# oresat0-mezzanine.net
KiCad netlist of a schematic drawn in EAGLE
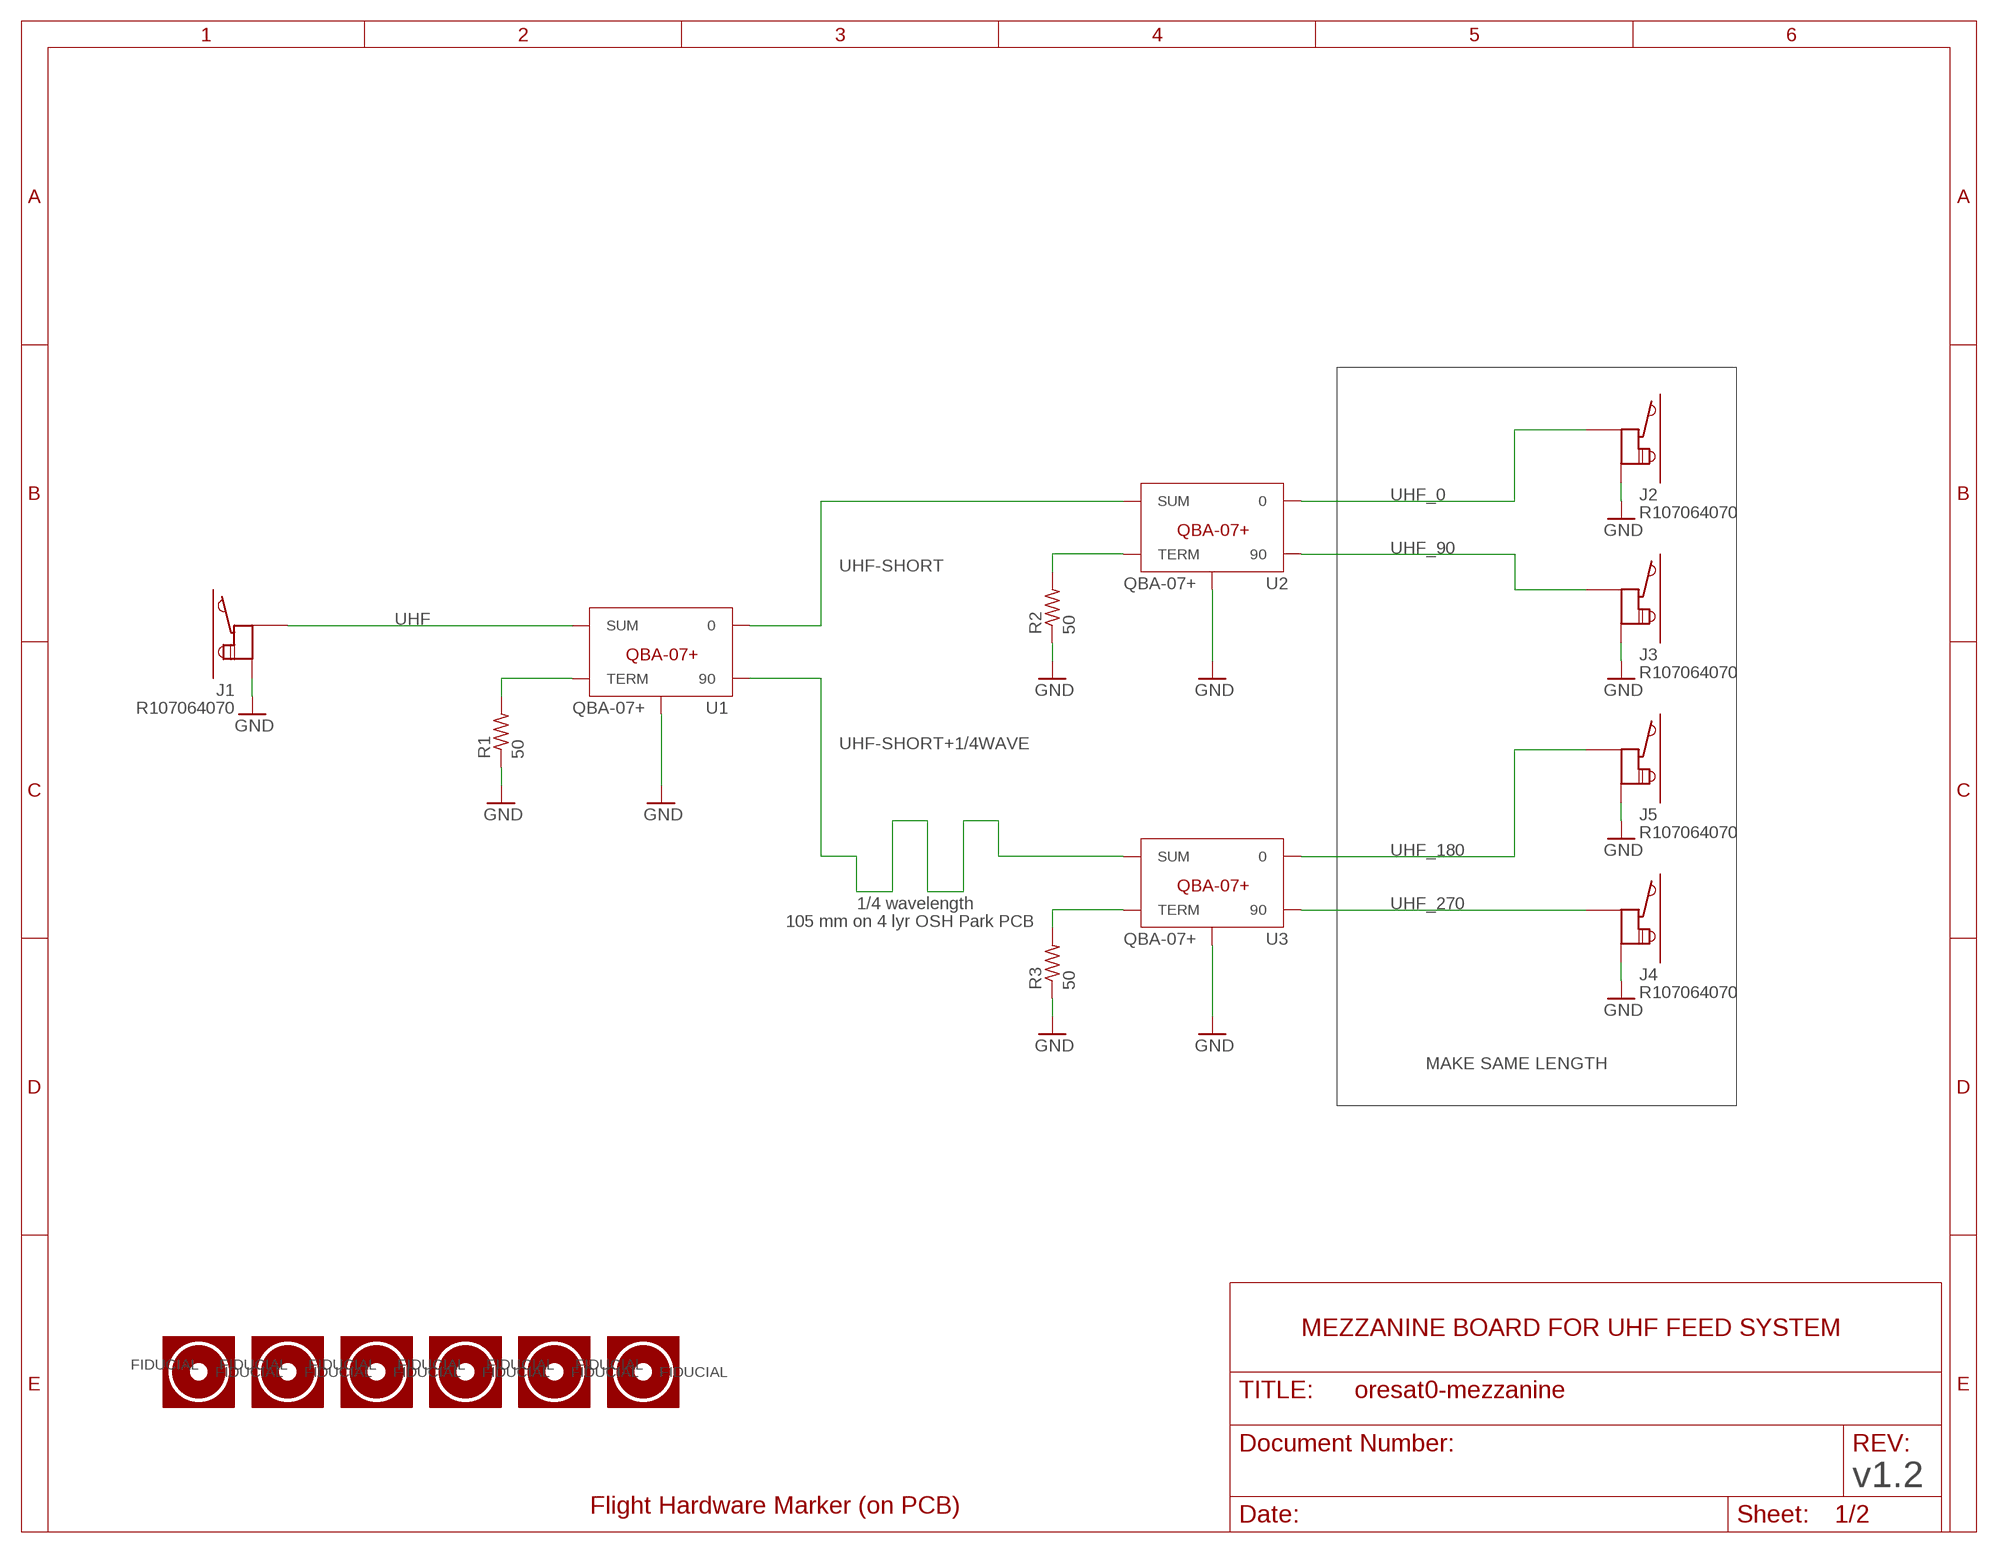
[diagram p0: schematic, sheet 1]
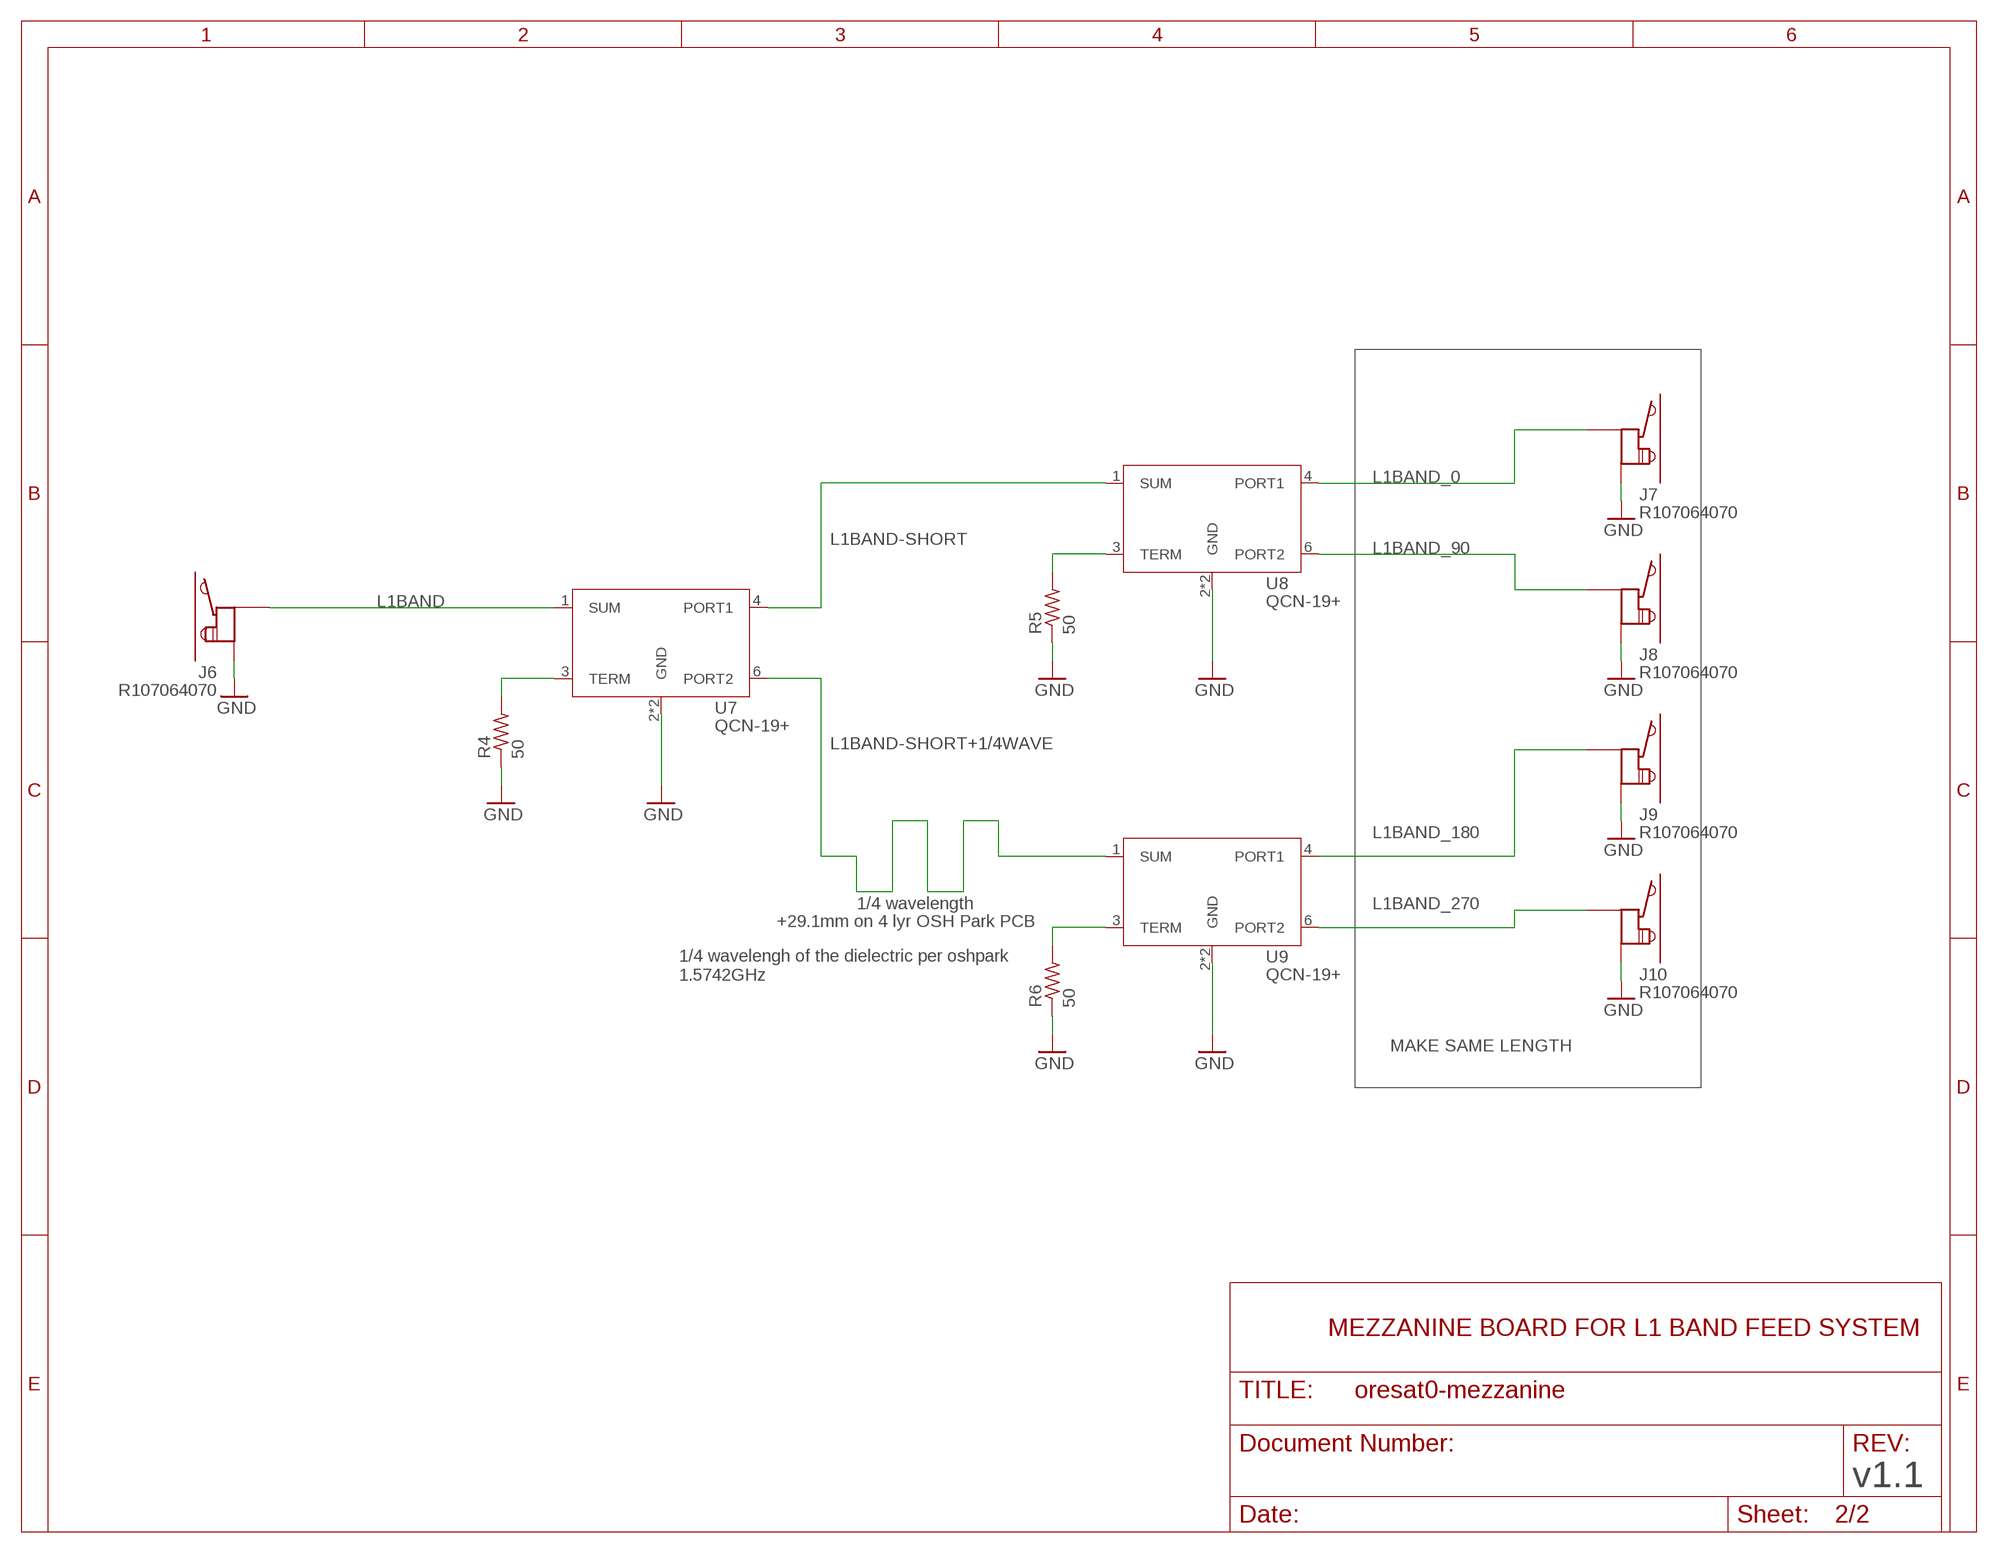
[diagram p1: schematic, sheet 2]

(export (version "E")
  (design (tool "Eeschema 10.0.6"))
  (components
    (comp (ref "J6")
      (value "R107064070")
      (footprint "eagle-import:R107064070_SOLDER")
      (fields (field (name "MFG") "Radiall"))
      (libsource (lib "eagle-import") (part "R107064070"))
    )
    (comp (ref "J7")
      (value "R107064070")
      (footprint "eagle-import:R107064070_SOLDER")
      (fields (field (name "MFG") "Radiall"))
      (libsource (lib "eagle-import") (part "R107064070"))
    )
    (comp (ref "J8")
      (value "R107064070")
      (footprint "eagle-import:R107064070_SOLDER")
      (fields (field (name "MFG") "Radiall"))
      (libsource (lib "eagle-import") (part "R107064070"))
    )
    (comp (ref "J9")
      (value "R107064070")
      (footprint "eagle-import:R107064070_SOLDER")
      (fields (field (name "MFG") "Radiall"))
      (libsource (lib "eagle-import") (part "R107064070"))
    )
    (comp (ref "J10")
      (value "R107064070")
      (footprint "eagle-import:R107064070_SOLDER")
      (fields (field (name "MFG") "Radiall"))
      (libsource (lib "eagle-import") (part "R107064070"))
    )
    (comp (ref "R4")
      (value "50")
      (footprint "eagle-import:.0603-C-NOSILK")
      (libsource (lib "eagle-import") (part "R-US_0603-C-NOSILK"))
    )
    (comp (ref "R5")
      (value "50")
      (footprint "eagle-import:.0603-C-NOSILK")
      (libsource (lib "eagle-import") (part "R-US_0603-C-NOSILK"))
    )
    (comp (ref "R6")
      (value "50")
      (footprint "eagle-import:.0603-C-NOSILK")
      (libsource (lib "eagle-import") (part "R-US_0603-C-NOSILK"))
    )
    (comp (ref "U7")
      (value "QCN-19+")
      (footprint "eagle-import:QCN-XXX+")
      (fields (field (name "MFG") "Mini-Circuits"))
      (libsource (lib "eagle-import") (part "QCN-XXX+"))
    )
    (comp (ref "U8")
      (value "QCN-19+")
      (footprint "eagle-import:QCN-XXX+")
      (fields (field (name "MFG") "Mini-Circuits"))
      (libsource (lib "eagle-import") (part "QCN-XXX+"))
    )
    (comp (ref "U9")
      (value "QCN-19+")
      (footprint "eagle-import:QCN-XXX+")
      (fields (field (name "MFG") "Mini-Circuits"))
      (libsource (lib "eagle-import") (part "QCN-XXX+"))
    )
    (comp (ref "FIDUCIAL1")
      (value "FIDUCIAL-1.0X2.0")
      (footprint "eagle-import:FIDUCIAL-1.0X2.0")
      (libsource (lib "eagle-import") (part "FIDUCIAL-1.0X2.0"))
    )
    (comp (ref "FIDUCIAL2")
      (value "FIDUCIAL-1.0X2.0")
      (footprint "eagle-import:FIDUCIAL-1.0X2.0")
      (libsource (lib "eagle-import") (part "FIDUCIAL-1.0X2.0"))
    )
    (comp (ref "FIDUCIAL3")
      (value "FIDUCIAL-1.0X2.0")
      (footprint "eagle-import:FIDUCIAL-1.0X2.0")
      (libsource (lib "eagle-import") (part "FIDUCIAL-1.0X2.0"))
    )
    (comp (ref "FIDUCIAL4")
      (value "FIDUCIAL-1.0X2.0")
      (footprint "eagle-import:FIDUCIAL-1.0X2.0")
      (libsource (lib "eagle-import") (part "FIDUCIAL-1.0X2.0"))
    )
    (comp (ref "FIDUCIAL6")
      (value "FIDUCIAL-1.0X2.0")
      (footprint "eagle-import:FIDUCIAL-1.0X2.0")
      (libsource (lib "eagle-import") (part "FIDUCIAL-1.0X2.0"))
    )
    (comp (ref "FIDUCIAL7")
      (value "FIDUCIAL-1.0X2.0")
      (footprint "eagle-import:FIDUCIAL-1.0X2.0")
      (libsource (lib "eagle-import") (part "FIDUCIAL-1.0X2.0"))
    )
    (comp (ref "J1")
      (value "R107064070")
      (footprint "eagle-import:R107064070_SOLDER")
      (fields (field (name "MFG") "Radiall"))
      (libsource (lib "eagle-import") (part "R107064070"))
    )
    (comp (ref "J2")
      (value "R107064070")
      (footprint "eagle-import:R107064070_SOLDER")
      (fields (field (name "MFG") "Radiall"))
      (libsource (lib "eagle-import") (part "R107064070"))
    )
    (comp (ref "J3")
      (value "R107064070")
      (footprint "eagle-import:R107064070_SOLDER")
      (fields (field (name "MFG") "Radiall"))
      (libsource (lib "eagle-import") (part "R107064070"))
    )
    (comp (ref "J4")
      (value "R107064070")
      (footprint "eagle-import:R107064070_SOLDER")
      (fields (field (name "MFG") "Radiall"))
      (libsource (lib "eagle-import") (part "R107064070"))
    )
    (comp (ref "J5")
      (value "R107064070")
      (footprint "eagle-import:R107064070_SOLDER")
      (fields (field (name "MFG") "Radiall"))
      (libsource (lib "eagle-import") (part "R107064070"))
    )
    (comp (ref "R1")
      (value "50")
      (footprint "eagle-import:.0603-C-NOSILK")
      (libsource (lib "eagle-import") (part "R-US_0603-C-NOSILK"))
    )
    (comp (ref "R2")
      (value "50")
      (footprint "eagle-import:.0603-C-NOSILK")
      (libsource (lib "eagle-import") (part "R-US_0603-C-NOSILK"))
    )
    (comp (ref "R3")
      (value "50")
      (footprint "eagle-import:.0603-C-NOSILK")
      (libsource (lib "eagle-import") (part "R-US_0603-C-NOSILK"))
    )
    (comp (ref "U$1")
      (value "FLIGHMARKERNEW")
      (footprint "eagle-import:FLIGHTMARKER_NEW_BOARDS")
      (libsource (lib "eagle-import") (part "FLIGHMARKERNEW"))
    )
    (comp (ref "U1")
      (value "QBA-07+")
      (footprint "eagle-import:QBA-07+")
      (libsource (lib "eagle-import") (part "QBA-07+"))
    )
    (comp (ref "U2")
      (value "QBA-07+")
      (footprint "eagle-import:QBA-07+")
      (libsource (lib "eagle-import") (part "QBA-07+"))
    )
    (comp (ref "U3")
      (value "QBA-07+")
      (footprint "eagle-import:QBA-07+")
      (libsource (lib "eagle-import") (part "QBA-07+"))
    )
  )
  (nets
    (net (code "1") (name "GND") (class "Default")
      (node (ref "J1") (pin "P$2") (pinfunction "P$2_P$2") (pintype "bidirectional"))
      (node (ref "J1") (pin "P$3") (pinfunction "P$2_P$3") (pintype "bidirectional"))
      (node (ref "J10") (pin "P$2") (pinfunction "P$2_P$2") (pintype "bidirectional"))
      (node (ref "J10") (pin "P$3") (pinfunction "P$2_P$3") (pintype "bidirectional"))
      (node (ref "J2") (pin "P$2") (pinfunction "P$2_P$2") (pintype "bidirectional"))
      (node (ref "J2") (pin "P$3") (pinfunction "P$2_P$3") (pintype "bidirectional"))
      (node (ref "J3") (pin "P$2") (pinfunction "P$2_P$2") (pintype "bidirectional"))
      (node (ref "J3") (pin "P$3") (pinfunction "P$2_P$3") (pintype "bidirectional"))
      (node (ref "J4") (pin "P$2") (pinfunction "P$2_P$2") (pintype "bidirectional"))
      (node (ref "J4") (pin "P$3") (pinfunction "P$2_P$3") (pintype "bidirectional"))
      (node (ref "J5") (pin "P$2") (pinfunction "P$2_P$2") (pintype "bidirectional"))
      (node (ref "J5") (pin "P$3") (pinfunction "P$2_P$3") (pintype "bidirectional"))
      (node (ref "J6") (pin "P$2") (pinfunction "P$2_P$2") (pintype "bidirectional"))
      (node (ref "J6") (pin "P$3") (pinfunction "P$2_P$3") (pintype "bidirectional"))
      (node (ref "J7") (pin "P$2") (pinfunction "P$2_P$2") (pintype "bidirectional"))
      (node (ref "J7") (pin "P$3") (pinfunction "P$2_P$3") (pintype "bidirectional"))
      (node (ref "J8") (pin "P$2") (pinfunction "P$2_P$2") (pintype "bidirectional"))
      (node (ref "J8") (pin "P$3") (pinfunction "P$2_P$3") (pintype "bidirectional"))
      (node (ref "J9") (pin "P$2") (pinfunction "P$2_P$2") (pintype "bidirectional"))
      (node (ref "J9") (pin "P$3") (pinfunction "P$2_P$3") (pintype "bidirectional"))
      (node (ref "R1") (pin "1") (pinfunction "1_1") (pintype "passive"))
      (node (ref "R2") (pin "1") (pinfunction "1_1") (pintype "passive"))
      (node (ref "R3") (pin "1") (pinfunction "1_1") (pintype "passive"))
      (node (ref "R4") (pin "1") (pinfunction "1_1") (pintype "passive"))
      (node (ref "R5") (pin "1") (pinfunction "1_1") (pintype "passive"))
      (node (ref "R6") (pin "1") (pinfunction "1_1") (pintype "passive"))
      (node (ref "U1") (pin "2") (pinfunction "GND_2") (pintype "power_in"))
      (node (ref "U1") (pin "3") (pinfunction "GND_3") (pintype "power_in"))
      (node (ref "U1") (pin "4") (pinfunction "GND_4") (pintype "power_in"))
      (node (ref "U1") (pin "7") (pinfunction "GND_7") (pintype "power_in"))
      (node (ref "U1") (pin "8") (pinfunction "GND_8") (pintype "power_in"))
      (node (ref "U1") (pin "9") (pinfunction "GND_9") (pintype "power_in"))
      (node (ref "U1") (pin "GND-NO-PAD") (pinfunction "GND_GND-NO-PAD") (pintype "power_in"))
      (node (ref "U2") (pin "2") (pinfunction "GND_2") (pintype "power_in"))
      (node (ref "U2") (pin "3") (pinfunction "GND_3") (pintype "power_in"))
      (node (ref "U2") (pin "4") (pinfunction "GND_4") (pintype "power_in"))
      (node (ref "U2") (pin "7") (pinfunction "GND_7") (pintype "power_in"))
      (node (ref "U2") (pin "8") (pinfunction "GND_8") (pintype "power_in"))
      (node (ref "U2") (pin "9") (pinfunction "GND_9") (pintype "power_in"))
      (node (ref "U2") (pin "GND-NO-PAD") (pinfunction "GND_GND-NO-PAD") (pintype "power_in"))
      (node (ref "U3") (pin "2") (pinfunction "GND_2") (pintype "power_in"))
      (node (ref "U3") (pin "3") (pinfunction "GND_3") (pintype "power_in"))
      (node (ref "U3") (pin "4") (pinfunction "GND_4") (pintype "power_in"))
      (node (ref "U3") (pin "7") (pinfunction "GND_7") (pintype "power_in"))
      (node (ref "U3") (pin "8") (pinfunction "GND_8") (pintype "power_in"))
      (node (ref "U3") (pin "9") (pinfunction "GND_9") (pintype "power_in"))
      (node (ref "U3") (pin "GND-NO-PAD") (pinfunction "GND_GND-NO-PAD") (pintype "power_in"))
      (node (ref "U7") (pin "2") (pinfunction "GND_2") (pintype "power_in"))
      (node (ref "U7") (pin "5") (pinfunction "GND_5") (pintype "power_in"))
      (node (ref "U8") (pin "2") (pinfunction "GND_2") (pintype "power_in"))
      (node (ref "U8") (pin "5") (pinfunction "GND_5") (pintype "power_in"))
      (node (ref "U9") (pin "2") (pinfunction "GND_2") (pintype "power_in"))
      (node (ref "U9") (pin "5") (pinfunction "GND_5") (pintype "power_in"))
    )
    (net (code "2") (name "L1BAND") (class "Default")
      (node (ref "J6") (pin "P$1") (pinfunction "P$1_P$1") (pintype "bidirectional"))
      (node (ref "U7") (pin "1") (pinfunction "SUM_1") (pintype "bidirectional"))
    )
    (net (code "3") (name "L1BAND-SHORT") (class "Default")
      (node (ref "U7") (pin "4") (pinfunction "PORT1_4") (pintype "bidirectional"))
      (node (ref "U8") (pin "1") (pinfunction "SUM_1") (pintype "bidirectional"))
    )
    (net (code "4") (name "L1BAND-SHORT+1{slash}4WAVE") (class "Default")
      (node (ref "U7") (pin "6") (pinfunction "PORT2_6") (pintype "bidirectional"))
      (node (ref "U9") (pin "1") (pinfunction "SUM_1") (pintype "bidirectional"))
    )
    (net (code "5") (name "L1BAND_0") (class "Default")
      (node (ref "J7") (pin "P$1") (pinfunction "P$1_P$1") (pintype "bidirectional"))
      (node (ref "U8") (pin "4") (pinfunction "PORT1_4") (pintype "bidirectional"))
    )
    (net (code "6") (name "L1BAND_90") (class "Default")
      (node (ref "J8") (pin "P$1") (pinfunction "P$1_P$1") (pintype "bidirectional"))
      (node (ref "U8") (pin "6") (pinfunction "PORT2_6") (pintype "bidirectional"))
    )
    (net (code "7") (name "L1BAND_180") (class "Default")
      (node (ref "J9") (pin "P$1") (pinfunction "P$1_P$1") (pintype "bidirectional"))
      (node (ref "U9") (pin "4") (pinfunction "PORT1_4") (pintype "bidirectional"))
    )
    (net (code "8") (name "L1BAND_270") (class "Default")
      (node (ref "J10") (pin "P$1") (pinfunction "P$1_P$1") (pintype "bidirectional"))
      (node (ref "U9") (pin "6") (pinfunction "PORT2_6") (pintype "bidirectional"))
    )
    (net (code "9") (name "Net-(U1-TERM)") (class "Default")
      (node (ref "R1") (pin "2") (pinfunction "2_2") (pintype "passive"))
      (node (ref "U1") (pin "5") (pinfunction "TERM_5") (pintype "passive"))
    )
    (net (code "10") (name "Net-(U2-TERM)") (class "Default")
      (node (ref "R2") (pin "2") (pinfunction "2_2") (pintype "passive"))
      (node (ref "U2") (pin "5") (pinfunction "TERM_5") (pintype "passive"))
    )
    (net (code "11") (name "Net-(U3-TERM)") (class "Default")
      (node (ref "R3") (pin "2") (pinfunction "2_2") (pintype "passive"))
      (node (ref "U3") (pin "5") (pinfunction "TERM_5") (pintype "passive"))
    )
    (net (code "12") (name "Net-(U7-TERM)") (class "Default")
      (node (ref "R4") (pin "2") (pinfunction "2_2") (pintype "passive"))
      (node (ref "U7") (pin "3") (pinfunction "TERM_3") (pintype "bidirectional"))
    )
    (net (code "13") (name "Net-(U8-TERM)") (class "Default")
      (node (ref "R5") (pin "2") (pinfunction "2_2") (pintype "passive"))
      (node (ref "U8") (pin "3") (pinfunction "TERM_3") (pintype "bidirectional"))
    )
    (net (code "14") (name "Net-(U9-TERM)") (class "Default")
      (node (ref "R6") (pin "2") (pinfunction "2_2") (pintype "passive"))
      (node (ref "U9") (pin "3") (pinfunction "TERM_3") (pintype "bidirectional"))
    )
    (net (code "15") (name "UHF") (class "Default")
      (node (ref "J1") (pin "P$1") (pinfunction "P$1_P$1") (pintype "bidirectional"))
      (node (ref "U1") (pin "1") (pinfunction "SUM_1") (pintype "passive"))
    )
    (net (code "16") (name "UHF-SHORT") (class "Default")
      (node (ref "U1") (pin "6") (pinfunction "0_6") (pintype "passive"))
      (node (ref "U2") (pin "1") (pinfunction "SUM_1") (pintype "passive"))
    )
    (net (code "17") (name "UHF-SHORT+1{slash}4WAVE") (class "Default")
      (node (ref "U1") (pin "10") (pinfunction "90_10") (pintype "passive"))
      (node (ref "U3") (pin "1") (pinfunction "SUM_1") (pintype "passive"))
    )
    (net (code "18") (name "UHF_0") (class "Default")
      (node (ref "J2") (pin "P$1") (pinfunction "P$1_P$1") (pintype "bidirectional"))
      (node (ref "U2") (pin "6") (pinfunction "0_6") (pintype "passive"))
    )
    (net (code "19") (name "UHF_90") (class "Default")
      (node (ref "J3") (pin "P$1") (pinfunction "P$1_P$1") (pintype "bidirectional"))
      (node (ref "U2") (pin "10") (pinfunction "90_10") (pintype "passive"))
    )
    (net (code "20") (name "UHF_180") (class "Default")
      (node (ref "J5") (pin "P$1") (pinfunction "P$1_P$1") (pintype "bidirectional"))
      (node (ref "U3") (pin "6") (pinfunction "0_6") (pintype "passive"))
    )
    (net (code "21") (name "UHF_270") (class "Default")
      (node (ref "J4") (pin "P$1") (pinfunction "P$1_P$1") (pintype "bidirectional"))
      (node (ref "U3") (pin "10") (pinfunction "90_10") (pintype "passive"))
    )
    (net (code "22") (name "unconnected-(FIDUCIAL1-PadFIDUCIAL)") (class "Default")
      (node (ref "FIDUCIAL1") (pin "FIDUCIAL") (pinfunction "FIDUCIAL_FIDUCIAL") (pintype "no_connect"))
    )
    (net (code "23") (name "unconnected-(FIDUCIAL2-PadFIDUCIAL)") (class "Default")
      (node (ref "FIDUCIAL2") (pin "FIDUCIAL") (pinfunction "FIDUCIAL_FIDUCIAL") (pintype "no_connect"))
    )
    (net (code "24") (name "unconnected-(FIDUCIAL3-PadFIDUCIAL)") (class "Default")
      (node (ref "FIDUCIAL3") (pin "FIDUCIAL") (pinfunction "FIDUCIAL_FIDUCIAL") (pintype "no_connect"))
    )
    (net (code "25") (name "unconnected-(FIDUCIAL4-PadFIDUCIAL)") (class "Default")
      (node (ref "FIDUCIAL4") (pin "FIDUCIAL") (pinfunction "FIDUCIAL_FIDUCIAL") (pintype "no_connect"))
    )
    (net (code "26") (name "unconnected-(FIDUCIAL6-PadFIDUCIAL)") (class "Default")
      (node (ref "FIDUCIAL6") (pin "FIDUCIAL") (pinfunction "FIDUCIAL_FIDUCIAL") (pintype "no_connect"))
    )
    (net (code "27") (name "unconnected-(FIDUCIAL7-PadFIDUCIAL)") (class "Default")
      (node (ref "FIDUCIAL7") (pin "FIDUCIAL") (pinfunction "FIDUCIAL_FIDUCIAL") (pintype "no_connect"))
    )
  )
)
